# connectors-dribbler.net
KiCad netlist of a schematic drawn in Altium Designer
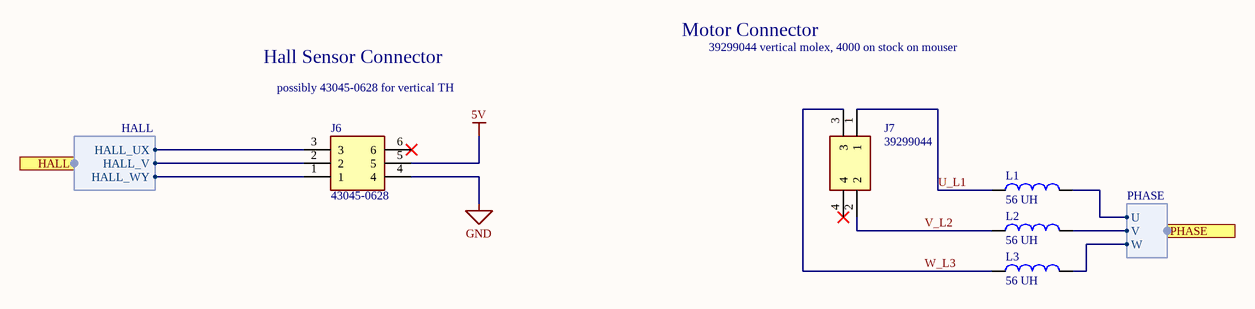
[diagram p0: connectors-dribbler.SchDoc]

(export (version "E")
  (design (tool "Eeschema 10.0.6"))
  (components
    (comp (ref "J6")
      (value "43045-0628")
      (footprint "430450628")
      (description "Molex 43045-0628 6POS Microfit\r\ndual row, Vertical")
      (fields (field (name "PART NUMBER") "CN HDR 6POS Molex 43045-0628"))
      (libsource (lib "Connector_Library") (part "CN HDR 6POS Molex 43045-0628"))
    )
    (comp (ref "J7")
      (value "39299044")
      (footprint "39299044")
      (description "Molex 39299044 4POS Minifit\r\ndual row, vertical")
      (fields (field (name "PART NUMBER") "CN HDR 4POS Molex 39299044 VERT"))
      (libsource (lib "Connector_Library") (part "CN HDR 4POS Molex 39299044 VERT"))
    )
    (comp (ref "L1")
      (value "56 UH")
      (footprint "EATON _HCM1A1307V2-560-R")
      (description "FIXED IND 56UH 4A 65 MOHM SMD Shielded - Inductor 65mOhm Max Nonstandard -")
      (fields (field (name "PART NUMBER") "IND 56UH 4A 65 mOHM SMD"))
      (libsource (lib "Inductor_Library") (part "IND 56UH 4A 65 mOHM SMD"))
    )
    (comp (ref "L2")
      (value "56 UH")
      (footprint "EATON _HCM1A1307V2-560-R")
      (description "FIXED IND 56UH 4A 65 MOHM SMD Shielded - Inductor 65mOhm Max Nonstandard -")
      (fields (field (name "PART NUMBER") "IND 56UH 4A 65 mOHM SMD"))
      (libsource (lib "Inductor_Library") (part "IND 56UH 4A 65 mOHM SMD"))
    )
    (comp (ref "L3")
      (value "56 UH")
      (footprint "EATON _HCM1A1307V2-560-R")
      (description "FIXED IND 56UH 4A 65 MOHM SMD Shielded - Inductor 65mOhm Max Nonstandard -")
      (fields (field (name "PART NUMBER") "IND 56UH 4A 65 mOHM SMD"))
      (libsource (lib "Inductor_Library") (part "IND 56UH 4A 65 mOHM SMD"))
    )
  )
  (nets
    (net (code "3") (name "/HALL_UX") (class "Default")
      (node (ref "J6") (pin "3") (pinfunction "3_3") (pintype "passive"))
    )
    (net (code "4") (name "/HALL_V") (class "Default")
      (node (ref "J6") (pin "2") (pinfunction "2_2") (pintype "passive"))
    )
    (net (code "5") (name "/HALL_WY") (class "Default")
      (node (ref "J6") (pin "1") (pinfunction "1_1") (pintype "passive"))
    )
    (net (code "6") (name "/U") (class "Default")
      (node (ref "L1") (pin "2") (pinfunction "2_2") (pintype "passive"))
    )
    (net (code "7") (name "/U_L1") (class "Default")
      (node (ref "J7") (pin "1") (pinfunction "1_1") (pintype "passive"))
      (node (ref "L1") (pin "1") (pinfunction "1_1") (pintype "passive"))
    )
    (net (code "8") (name "/V") (class "Default")
      (node (ref "L2") (pin "2") (pinfunction "2_2") (pintype "passive"))
    )
    (net (code "9") (name "/V_L2") (class "Default")
      (node (ref "J7") (pin "2") (pinfunction "2_2") (pintype "passive"))
      (node (ref "L2") (pin "1") (pinfunction "1_1") (pintype "passive"))
    )
    (net (code "10") (name "/W") (class "Default")
      (node (ref "L3") (pin "2") (pinfunction "2_2") (pintype "passive"))
    )
    (net (code "11") (name "/W_L3") (class "Default")
      (node (ref "J7") (pin "3") (pinfunction "3_3") (pintype "passive"))
      (node (ref "L3") (pin "1") (pinfunction "1_1") (pintype "passive"))
    )
    (net (code "14") (name "5V") (class "Default")
      (node (ref "J6") (pin "5") (pinfunction "5_5") (pintype "passive"))
    )
    (net (code "15") (name "GND") (class "Default")
      (node (ref "J6") (pin "4") (pinfunction "4_4") (pintype "passive"))
    )
    (net (code "16") (name "unconnected-(J6-Pad6)") (class "Default")
      (node (ref "J6") (pin "6") (pinfunction "6_6") (pintype "passive+no_connect"))
    )
    (net (code "17") (name "unconnected-(J7-Pad4)") (class "Default")
      (node (ref "J7") (pin "4") (pinfunction "4_4") (pintype "passive+no_connect"))
    )
  )
)
